# MCU.net
KiCad netlist of a schematic drawn in Altium Designer
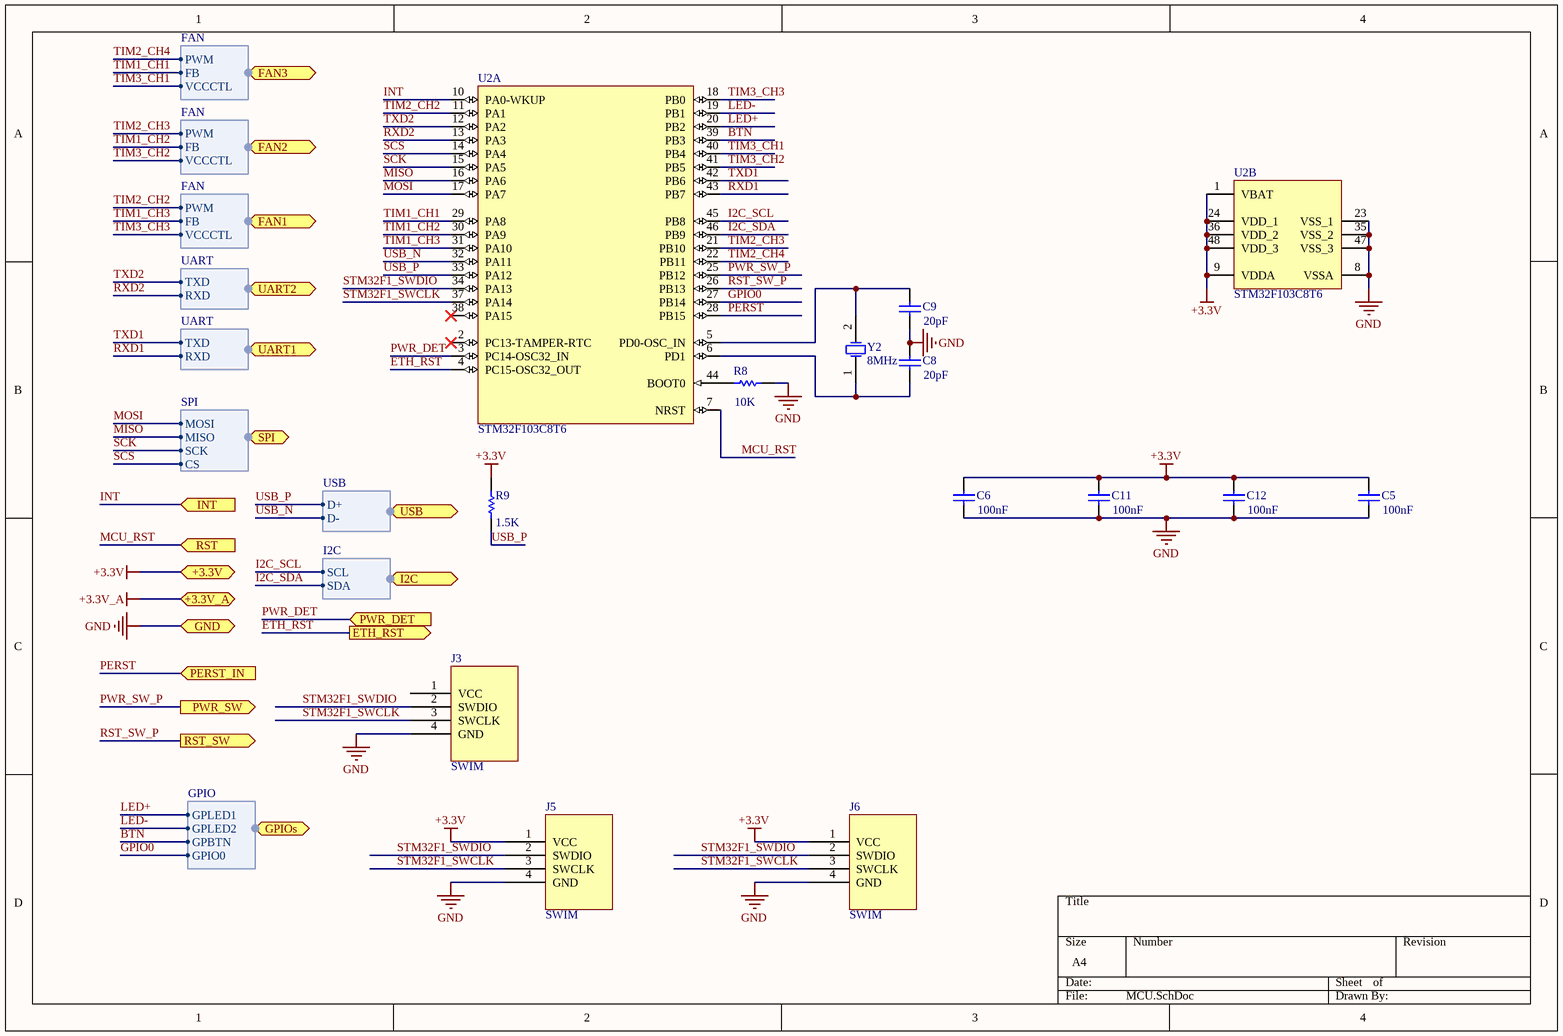
[diagram p0: MCU.SchDoc]

(export (version "E")
  (design (tool "Eeschema 10.0.6"))
  (components
    (comp (ref "C5")
      (value "100nF")
      (footprint "C-1608[0603]")
      (description "Capacitor (Semiconductor SIM Model)")
      (fields (field (name "PUBLISHER") "Altium Limited"))
      (libsource (lib "Miscellaneous Devices") (part "Cap Semi"))
    )
    (comp (ref "C6")
      (value "100nF")
      (footprint "C-1608[0603]")
      (description "Capacitor (Semiconductor SIM Model)")
      (fields (field (name "PUBLISHER") "Altium Limited"))
      (libsource (lib "Miscellaneous Devices") (part "Cap Semi"))
    )
    (comp (ref "C8")
      (value "20pF")
      (footprint "C-1608[0603]")
      (description "Capacitor (Semiconductor SIM Model)")
      (fields (field (name "PUBLISHER") "Altium Limited"))
      (libsource (lib "Miscellaneous Devices") (part "Cap Semi"))
    )
    (comp (ref "C9")
      (value "20pF")
      (footprint "C-1608[0603]")
      (description "Capacitor (Semiconductor SIM Model)")
      (fields (field (name "PUBLISHER") "Altium Limited"))
      (libsource (lib "Miscellaneous Devices") (part "Cap Semi"))
    )
    (comp (ref "C11")
      (value "100nF")
      (footprint "C-1608[0603]")
      (description "Capacitor (Semiconductor SIM Model)")
      (fields (field (name "PUBLISHER") "Altium Limited"))
      (libsource (lib "Miscellaneous Devices") (part "Cap Semi"))
    )
    (comp (ref "C12")
      (value "100nF")
      (footprint "C-1608[0603]")
      (description "Capacitor (Semiconductor SIM Model)")
      (fields (field (name "PUBLISHER") "Altium Limited"))
      (libsource (lib "Miscellaneous Devices") (part "Cap Semi"))
    )
    (comp (ref "J3") (value "SWIM") (footprint "SIP4") (libsource (lib "CPUBoard") (part "SWD")))
    (comp (ref "J5") (value "SWIM") (footprint "SWD_SOCKET") (libsource (lib "CPUBoard") (part "SWD")))
    (comp (ref "J6") (value "SWIM") (footprint "SWD_HEADER") (libsource (lib "CPUBoard") (part "SWD")))
    (comp (ref "R8")
      (value "10K")
      (footprint "R-1608[0603]")
      (description "Semiconductor Resistor")
      (fields (field (name "PUBLISHER") "Altium Limited"))
      (libsource (lib "Miscellaneous Devices") (part "Res Semi"))
    )
    (comp (ref "R9")
      (value "1.5K")
      (footprint "R-1608[0603]")
      (description "Semiconductor Resistor")
      (fields (field (name "PUBLISHER") "Altium Limited"))
      (libsource (lib "Miscellaneous Devices") (part "Res Semi"))
    )
    (comp (ref "U2")
      (value "STM32F103C8T6")
      (footprint "TQFP48_N")
      (description "ARM")
      (libsource (lib "Miscellaneous Devices LC") (part "STM32F103C8T6"))
    )
    (comp (ref "Y2")
      (value "8MHz")
      (footprint "LC-SMD-5032_2P")
      (description "Crystal Oscillator")
      (fields (field (name "PUBLISHER") "Altium Limited"))
      (libsource (lib "Miscellaneous Devices") (part "XTAL"))
    )
  )
  (nets
    (net (code "7") (name "+3.3V") (class "Default")
      (node (ref "C11") (pin "2") (pinfunction "2_2") (pintype "passive"))
      (node (ref "C12") (pin "2") (pinfunction "2_2") (pintype "passive"))
      (node (ref "C5") (pin "2") (pinfunction "2_2") (pintype "passive"))
      (node (ref "C6") (pin "2") (pinfunction "2_2") (pintype "passive"))
      (node (ref "J5") (pin "1") (pinfunction "VCC_1") (pintype "passive"))
      (node (ref "J6") (pin "1") (pinfunction "VCC_1") (pintype "passive"))
      (node (ref "R9") (pin "2") (pinfunction "2_2") (pintype "passive"))
      (node (ref "U2") (pin "1") (pinfunction "VBAT_1") (pintype "power_in"))
      (node (ref "U2") (pin "24") (pinfunction "VDD_1_24") (pintype "power_in"))
      (node (ref "U2") (pin "36") (pinfunction "VDD_2_36") (pintype "power_in"))
      (node (ref "U2") (pin "48") (pinfunction "VDD_3_48") (pintype "power_in"))
      (node (ref "U2") (pin "9") (pinfunction "VDDA_9") (pintype "power_in"))
    )
    (net (code "9") (name "/BTN") (class "Default")
      (node (ref "U2") (pin "39") (pinfunction "PB3_39") (pintype "bidirectional"))
    )
    (net (code "10") (name "/ETH_RST") (class "Default")
      (node (ref "U2") (pin "4") (pinfunction "PC15-OSC32_OUT_4") (pintype "bidirectional"))
    )
    (net (code "11") (name "/GPIO0") (class "Default")
      (node (ref "U2") (pin "27") (pinfunction "PB14_27") (pintype "bidirectional"))
    )
    (net (code "12") (name "/I2C_SCL") (class "Default")
      (node (ref "U2") (pin "45") (pinfunction "PB8_45") (pintype "bidirectional"))
    )
    (net (code "13") (name "/I2C_SDA") (class "Default")
      (node (ref "U2") (pin "46") (pinfunction "PB9_46") (pintype "bidirectional"))
    )
    (net (code "14") (name "/INT") (class "Default")
      (node (ref "U2") (pin "10") (pinfunction "PA0-WKUP_10") (pintype "bidirectional"))
    )
    (net (code "15") (name "/LED+") (class "Default")
      (node (ref "U2") (pin "20") (pinfunction "PB2_20") (pintype "bidirectional"))
    )
    (net (code "16") (name "/LED-") (class "Default")
      (node (ref "U2") (pin "19") (pinfunction "PB1_19") (pintype "bidirectional"))
    )
    (net (code "17") (name "/MCU_RST") (class "Default")
      (node (ref "U2") (pin "7") (pinfunction "NRST_7") (pintype "bidirectional"))
    )
    (net (code "18") (name "/MISO") (class "Default")
      (node (ref "U2") (pin "16") (pinfunction "PA6_16") (pintype "bidirectional"))
    )
    (net (code "19") (name "/MOSI") (class "Default")
      (node (ref "U2") (pin "17") (pinfunction "PA7_17") (pintype "bidirectional"))
    )
    (net (code "20") (name "/PERST") (class "Default")
      (node (ref "U2") (pin "28") (pinfunction "PB15_28") (pintype "bidirectional"))
    )
    (net (code "21") (name "/PWR_DET") (class "Default")
      (node (ref "U2") (pin "3") (pinfunction "PC14-OSC32_IN_3") (pintype "bidirectional"))
    )
    (net (code "22") (name "/PWR_SW_P") (class "Default")
      (node (ref "U2") (pin "25") (pinfunction "PB12_25") (pintype "bidirectional"))
    )
    (net (code "23") (name "/RST_SW_P") (class "Default")
      (node (ref "U2") (pin "26") (pinfunction "PB13_26") (pintype "bidirectional"))
    )
    (net (code "24") (name "/RXD1") (class "Default")
      (node (ref "U2") (pin "43") (pinfunction "PB7_43") (pintype "bidirectional"))
    )
    (net (code "25") (name "/RXD2") (class "Default")
      (node (ref "U2") (pin "13") (pinfunction "PA3_13") (pintype "bidirectional"))
    )
    (net (code "26") (name "/SCK") (class "Default")
      (node (ref "U2") (pin "15") (pinfunction "PA5_15") (pintype "bidirectional"))
    )
    (net (code "27") (name "/SCS") (class "Default")
      (node (ref "U2") (pin "14") (pinfunction "PA4_14") (pintype "bidirectional"))
    )
    (net (code "28") (name "/STM32F1_SWCLK") (class "Default")
      (node (ref "J3") (pin "3") (pinfunction "SWCLK_3") (pintype "passive"))
      (node (ref "J5") (pin "3") (pinfunction "SWCLK_3") (pintype "passive"))
      (node (ref "J6") (pin "3") (pinfunction "SWCLK_3") (pintype "passive"))
      (node (ref "U2") (pin "37") (pinfunction "PA14_37") (pintype "bidirectional"))
    )
    (net (code "29") (name "/STM32F1_SWDIO") (class "Default")
      (node (ref "J3") (pin "2") (pinfunction "SWDIO_2") (pintype "passive"))
      (node (ref "J5") (pin "2") (pinfunction "SWDIO_2") (pintype "passive"))
      (node (ref "J6") (pin "2") (pinfunction "SWDIO_2") (pintype "passive"))
      (node (ref "U2") (pin "34") (pinfunction "PA13_34") (pintype "bidirectional"))
    )
    (net (code "30") (name "/TIM1_CH1") (class "Default")
      (node (ref "U2") (pin "29") (pinfunction "PA8_29") (pintype "bidirectional"))
    )
    (net (code "31") (name "/TIM1_CH2") (class "Default")
      (node (ref "U2") (pin "30") (pinfunction "PA9_30") (pintype "bidirectional"))
    )
    (net (code "32") (name "/TIM1_CH3") (class "Default")
      (node (ref "U2") (pin "31") (pinfunction "PA10_31") (pintype "bidirectional"))
    )
    (net (code "33") (name "/TIM2_CH2") (class "Default")
      (node (ref "U2") (pin "11") (pinfunction "PA1_11") (pintype "bidirectional"))
    )
    (net (code "34") (name "/TIM2_CH3") (class "Default")
      (node (ref "U2") (pin "21") (pinfunction "PB10_21") (pintype "bidirectional"))
    )
    (net (code "35") (name "/TIM2_CH4") (class "Default")
      (node (ref "U2") (pin "22") (pinfunction "PB11_22") (pintype "bidirectional"))
    )
    (net (code "36") (name "/TIM3_CH1") (class "Default")
      (node (ref "U2") (pin "40") (pinfunction "PB4_40") (pintype "bidirectional"))
    )
    (net (code "37") (name "/TIM3_CH2") (class "Default")
      (node (ref "U2") (pin "41") (pinfunction "PB5_41") (pintype "bidirectional"))
    )
    (net (code "38") (name "/TIM3_CH3") (class "Default")
      (node (ref "U2") (pin "18") (pinfunction "PB0_18") (pintype "bidirectional"))
    )
    (net (code "39") (name "/TXD1") (class "Default")
      (node (ref "U2") (pin "42") (pinfunction "PB6_42") (pintype "bidirectional"))
    )
    (net (code "40") (name "/TXD2") (class "Default")
      (node (ref "U2") (pin "12") (pinfunction "PA2_12") (pintype "bidirectional"))
    )
    (net (code "41") (name "/USB_N") (class "Default")
      (node (ref "U2") (pin "32") (pinfunction "PA11_32") (pintype "bidirectional"))
    )
    (net (code "42") (name "/USB_P") (class "Default")
      (node (ref "R9") (pin "1") (pinfunction "1_1") (pintype "passive"))
      (node (ref "U2") (pin "33") (pinfunction "PA12_33") (pintype "bidirectional"))
    )
    (net (code "49") (name "GND") (class "Default")
      (node (ref "C11") (pin "1") (pinfunction "1_1") (pintype "passive"))
      (node (ref "C12") (pin "1") (pinfunction "1_1") (pintype "passive"))
      (node (ref "C5") (pin "1") (pinfunction "1_1") (pintype "passive"))
      (node (ref "C6") (pin "1") (pinfunction "1_1") (pintype "passive"))
      (node (ref "C8") (pin "2") (pinfunction "2_2") (pintype "passive"))
      (node (ref "C9") (pin "1") (pinfunction "1_1") (pintype "passive"))
      (node (ref "J3") (pin "4") (pinfunction "GND_4") (pintype "passive"))
      (node (ref "J5") (pin "4") (pinfunction "GND_4") (pintype "passive"))
      (node (ref "J6") (pin "4") (pinfunction "GND_4") (pintype "passive"))
      (node (ref "R8") (pin "2") (pinfunction "2_2") (pintype "passive"))
      (node (ref "U2") (pin "23") (pinfunction "VSS_1_23") (pintype "power_in"))
      (node (ref "U2") (pin "35") (pinfunction "VSS_2_35") (pintype "power_in"))
      (node (ref "U2") (pin "47") (pinfunction "VSS_3_47") (pintype "power_in"))
      (node (ref "U2") (pin "8") (pinfunction "VSSA_8") (pintype "power_in"))
    )
    (net (code "50") (name "Net-(U2A-BOOT0)") (class "Default")
      (node (ref "R8") (pin "1") (pinfunction "1_1") (pintype "passive"))
      (node (ref "U2") (pin "44") (pinfunction "BOOT0_44") (pintype "input"))
    )
    (net (code "51") (name "Net-(U2A-PD0-OSC_IN)") (class "Default")
      (node (ref "C9") (pin "2") (pinfunction "2_2") (pintype "passive"))
      (node (ref "U2") (pin "5") (pinfunction "PD0-OSC_IN_5") (pintype "bidirectional"))
      (node (ref "Y2") (pin "2") (pinfunction "OSC2_2") (pintype "passive"))
    )
    (net (code "52") (name "Net-(U2A-PD1)") (class "Default")
      (node (ref "C8") (pin "1") (pinfunction "1_1") (pintype "passive"))
      (node (ref "U2") (pin "6") (pinfunction "PD1_6") (pintype "bidirectional"))
      (node (ref "Y2") (pin "1") (pinfunction "OSC1_1") (pintype "passive"))
    )
    (net (code "53") (name "unconnected-(J3-VCC-Pad1)") (class "Default")
      (node (ref "J3") (pin "1") (pinfunction "VCC_1") (pintype "passive"))
    )
    (net (code "54") (name "unconnected-(U2A-PA15-Pad38)") (class "Default")
      (node (ref "U2") (pin "38") (pinfunction "PA15_38") (pintype "bidirectional+no_connect"))
    )
    (net (code "55") (name "unconnected-(U2A-PC13-TAMPER-RTC-Pad2)") (class "Default")
      (node (ref "U2") (pin "2") (pinfunction "PC13-TAMPER-RTC_2") (pintype "bidirectional+no_connect"))
    )
  )
)
